# W964.net
KiCad netlist of a schematic drawn in EAGLE
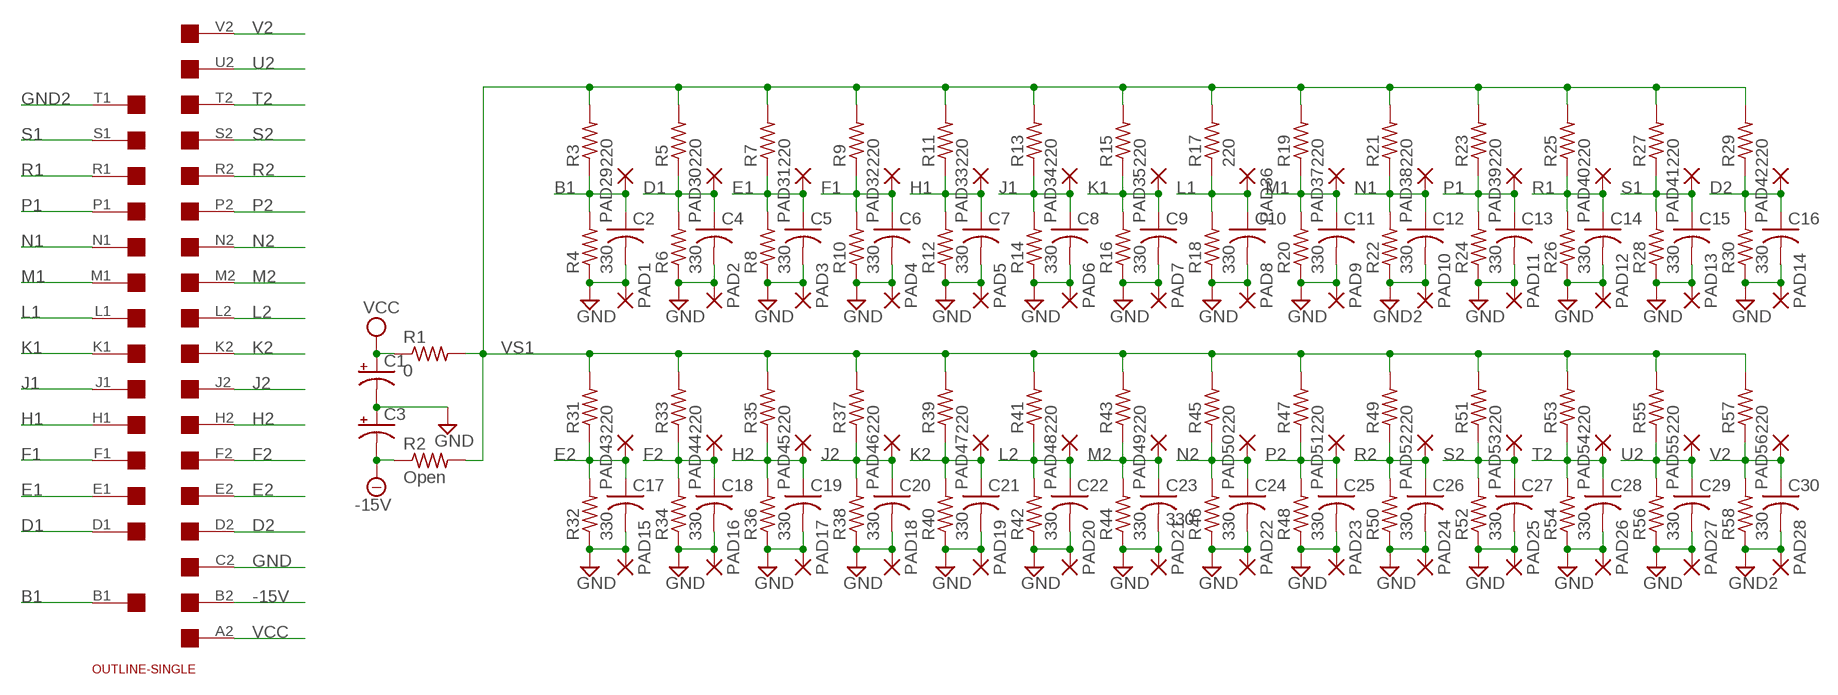
[diagram p0: schematic, sheet 1]

(export (version "E")
  (design (tool "Eeschema 10.0.6"))
  (components
    (comp (ref "C1")
      (value "CPOL-USE22-6AXIAL")
      (footprint "eagle-import:E22-6")
      (libsource (lib "eagle-import") (part "CPOL-USE22-6AXIAL"))
    )
    (comp (ref "C2")
      (value "C-US050-025X075")
      (footprint "eagle-import:C050-025X075")
      (libsource (lib "eagle-import") (part "C-US050-025X075"))
    )
    (comp (ref "C3")
      (value "CPOL-USE22-6AXIAL")
      (footprint "eagle-import:E22-6")
      (libsource (lib "eagle-import") (part "CPOL-USE22-6AXIAL"))
    )
    (comp (ref "C4")
      (value "C-US050-025X075")
      (footprint "eagle-import:C050-025X075")
      (libsource (lib "eagle-import") (part "C-US050-025X075"))
    )
    (comp (ref "C5")
      (value "C-US050-025X075")
      (footprint "eagle-import:C050-025X075")
      (libsource (lib "eagle-import") (part "C-US050-025X075"))
    )
    (comp (ref "C6")
      (value "C-US050-025X075")
      (footprint "eagle-import:C050-025X075")
      (libsource (lib "eagle-import") (part "C-US050-025X075"))
    )
    (comp (ref "C7")
      (value "C-US050-025X075")
      (footprint "eagle-import:C050-025X075")
      (libsource (lib "eagle-import") (part "C-US050-025X075"))
    )
    (comp (ref "C8")
      (value "C-US050-025X075")
      (footprint "eagle-import:C050-025X075")
      (libsource (lib "eagle-import") (part "C-US050-025X075"))
    )
    (comp (ref "C9")
      (value "C-US050-025X075")
      (footprint "eagle-import:C050-025X075")
      (libsource (lib "eagle-import") (part "C-US050-025X075"))
    )
    (comp (ref "C10")
      (value "C-US050-025X075")
      (footprint "eagle-import:C050-025X075")
      (libsource (lib "eagle-import") (part "C-US050-025X075"))
    )
    (comp (ref "C11")
      (value "C-US050-025X075")
      (footprint "eagle-import:C050-025X075")
      (libsource (lib "eagle-import") (part "C-US050-025X075"))
    )
    (comp (ref "C12")
      (value "C-US050-025X075")
      (footprint "eagle-import:C050-025X075")
      (libsource (lib "eagle-import") (part "C-US050-025X075"))
    )
    (comp (ref "C13")
      (value "C-US050-025X075")
      (footprint "eagle-import:C050-025X075")
      (libsource (lib "eagle-import") (part "C-US050-025X075"))
    )
    (comp (ref "C14")
      (value "C-US050-025X075")
      (footprint "eagle-import:C050-025X075")
      (libsource (lib "eagle-import") (part "C-US050-025X075"))
    )
    (comp (ref "C15")
      (value "C-US050-025X075")
      (footprint "eagle-import:C050-025X075")
      (libsource (lib "eagle-import") (part "C-US050-025X075"))
    )
    (comp (ref "C16")
      (value "C-US050-025X075")
      (footprint "eagle-import:C050-025X075")
      (libsource (lib "eagle-import") (part "C-US050-025X075"))
    )
    (comp (ref "C17")
      (value "C-US050-025X075")
      (footprint "eagle-import:C050-025X075")
      (libsource (lib "eagle-import") (part "C-US050-025X075"))
    )
    (comp (ref "C18")
      (value "C-US050-025X075")
      (footprint "eagle-import:C050-025X075")
      (libsource (lib "eagle-import") (part "C-US050-025X075"))
    )
    (comp (ref "C19")
      (value "C-US050-025X075")
      (footprint "eagle-import:C050-025X075")
      (libsource (lib "eagle-import") (part "C-US050-025X075"))
    )
    (comp (ref "C20")
      (value "C-US050-025X075")
      (footprint "eagle-import:C050-025X075")
      (libsource (lib "eagle-import") (part "C-US050-025X075"))
    )
    (comp (ref "C21")
      (value "C-US050-025X075")
      (footprint "eagle-import:C050-025X075")
      (libsource (lib "eagle-import") (part "C-US050-025X075"))
    )
    (comp (ref "C22")
      (value "C-US050-025X075")
      (footprint "eagle-import:C050-025X075")
      (libsource (lib "eagle-import") (part "C-US050-025X075"))
    )
    (comp (ref "C23")
      (value "330")
      (footprint "eagle-import:C050-025X075")
      (libsource (lib "eagle-import") (part "C-US050-025X075"))
    )
    (comp (ref "C24")
      (value "C-US050-025X075")
      (footprint "eagle-import:C050-025X075")
      (libsource (lib "eagle-import") (part "C-US050-025X075"))
    )
    (comp (ref "C25")
      (value "C-US050-025X075")
      (footprint "eagle-import:C050-025X075")
      (libsource (lib "eagle-import") (part "C-US050-025X075"))
    )
    (comp (ref "C26")
      (value "C-US050-025X075")
      (footprint "eagle-import:C050-025X075")
      (libsource (lib "eagle-import") (part "C-US050-025X075"))
    )
    (comp (ref "C27")
      (value "C-US050-025X075")
      (footprint "eagle-import:C050-025X075")
      (libsource (lib "eagle-import") (part "C-US050-025X075"))
    )
    (comp (ref "C28")
      (value "C-US050-025X075")
      (footprint "eagle-import:C050-025X075")
      (libsource (lib "eagle-import") (part "C-US050-025X075"))
    )
    (comp (ref "C29")
      (value "C-US050-025X075")
      (footprint "eagle-import:C050-025X075")
      (libsource (lib "eagle-import") (part "C-US050-025X075"))
    )
    (comp (ref "C30")
      (value "C-US050-025X075")
      (footprint "eagle-import:C050-025X075")
      (libsource (lib "eagle-import") (part "C-US050-025X075"))
    )
    (comp (ref "PAD1")
      (value "1,6/0,9")
      (footprint "eagle-import:1,6_0,9")
      (libsource (lib "eagle-import") (part "1,6/0,9"))
    )
    (comp (ref "PAD2")
      (value "1,6/0,9")
      (footprint "eagle-import:1,6_0,9")
      (libsource (lib "eagle-import") (part "1,6/0,9"))
    )
    (comp (ref "PAD3")
      (value "1,6/0,9")
      (footprint "eagle-import:1,6_0,9")
      (libsource (lib "eagle-import") (part "1,6/0,9"))
    )
    (comp (ref "PAD4")
      (value "1,6/0,9")
      (footprint "eagle-import:1,6_0,9")
      (libsource (lib "eagle-import") (part "1,6/0,9"))
    )
    (comp (ref "PAD5")
      (value "1,6/0,9")
      (footprint "eagle-import:1,6_0,9")
      (libsource (lib "eagle-import") (part "1,6/0,9"))
    )
    (comp (ref "PAD6")
      (value "1,6/0,9")
      (footprint "eagle-import:1,6_0,9")
      (libsource (lib "eagle-import") (part "1,6/0,9"))
    )
    (comp (ref "PAD7")
      (value "1,6/0,9")
      (footprint "eagle-import:1,6_0,9")
      (libsource (lib "eagle-import") (part "1,6/0,9"))
    )
    (comp (ref "PAD8")
      (value "1,6/0,9")
      (footprint "eagle-import:1,6_0,9")
      (libsource (lib "eagle-import") (part "1,6/0,9"))
    )
    (comp (ref "PAD9")
      (value "1,6/0,9")
      (footprint "eagle-import:1,6_0,9")
      (libsource (lib "eagle-import") (part "1,6/0,9"))
    )
    (comp (ref "PAD10")
      (value "1,6/0,9")
      (footprint "eagle-import:1,6_0,9")
      (libsource (lib "eagle-import") (part "1,6/0,9"))
    )
    (comp (ref "PAD11")
      (value "1,6/0,9")
      (footprint "eagle-import:1,6_0,9")
      (libsource (lib "eagle-import") (part "1,6/0,9"))
    )
    (comp (ref "PAD12")
      (value "1,6/0,9")
      (footprint "eagle-import:1,6_0,9")
      (libsource (lib "eagle-import") (part "1,6/0,9"))
    )
    (comp (ref "PAD13")
      (value "1,6/0,9")
      (footprint "eagle-import:1,6_0,9")
      (libsource (lib "eagle-import") (part "1,6/0,9"))
    )
    (comp (ref "PAD14")
      (value "1,6/0,9")
      (footprint "eagle-import:1,6_0,9")
      (libsource (lib "eagle-import") (part "1,6/0,9"))
    )
    (comp (ref "PAD15")
      (value "1,6/0,9")
      (footprint "eagle-import:1,6_0,9")
      (libsource (lib "eagle-import") (part "1,6/0,9"))
    )
    (comp (ref "PAD16")
      (value "1,6/0,9")
      (footprint "eagle-import:1,6_0,9")
      (libsource (lib "eagle-import") (part "1,6/0,9"))
    )
    (comp (ref "PAD17")
      (value "1,6/0,9")
      (footprint "eagle-import:1,6_0,9")
      (libsource (lib "eagle-import") (part "1,6/0,9"))
    )
    (comp (ref "PAD18")
      (value "1,6/0,9")
      (footprint "eagle-import:1,6_0,9")
      (libsource (lib "eagle-import") (part "1,6/0,9"))
    )
    (comp (ref "PAD19")
      (value "1,6/0,9")
      (footprint "eagle-import:1,6_0,9")
      (libsource (lib "eagle-import") (part "1,6/0,9"))
    )
    (comp (ref "PAD20")
      (value "1,6/0,9")
      (footprint "eagle-import:1,6_0,9")
      (libsource (lib "eagle-import") (part "1,6/0,9"))
    )
    (comp (ref "PAD21")
      (value "1,6/0,9")
      (footprint "eagle-import:1,6_0,9")
      (libsource (lib "eagle-import") (part "1,6/0,9"))
    )
    (comp (ref "PAD22")
      (value "1,6/0,9")
      (footprint "eagle-import:1,6_0,9")
      (libsource (lib "eagle-import") (part "1,6/0,9"))
    )
    (comp (ref "PAD23")
      (value "1,6/0,9")
      (footprint "eagle-import:1,6_0,9")
      (libsource (lib "eagle-import") (part "1,6/0,9"))
    )
    (comp (ref "PAD24")
      (value "1,6/0,9")
      (footprint "eagle-import:1,6_0,9")
      (libsource (lib "eagle-import") (part "1,6/0,9"))
    )
    (comp (ref "PAD25")
      (value "1,6/0,9")
      (footprint "eagle-import:1,6_0,9")
      (libsource (lib "eagle-import") (part "1,6/0,9"))
    )
    (comp (ref "PAD26")
      (value "1,6/0,9")
      (footprint "eagle-import:1,6_0,9")
      (libsource (lib "eagle-import") (part "1,6/0,9"))
    )
    (comp (ref "PAD27")
      (value "1,6/0,9")
      (footprint "eagle-import:1,6_0,9")
      (libsource (lib "eagle-import") (part "1,6/0,9"))
    )
    (comp (ref "PAD28")
      (value "1,6/0,9")
      (footprint "eagle-import:1,6_0,9")
      (libsource (lib "eagle-import") (part "1,6/0,9"))
    )
    (comp (ref "PAD29")
      (value "1,6/0,9")
      (footprint "eagle-import:1,6_0,9")
      (libsource (lib "eagle-import") (part "1,6/0,9"))
    )
    (comp (ref "PAD30")
      (value "1,6/0,9")
      (footprint "eagle-import:1,6_0,9")
      (libsource (lib "eagle-import") (part "1,6/0,9"))
    )
    (comp (ref "PAD31")
      (value "1,6/0,9")
      (footprint "eagle-import:1,6_0,9")
      (libsource (lib "eagle-import") (part "1,6/0,9"))
    )
    (comp (ref "PAD32")
      (value "1,6/0,9")
      (footprint "eagle-import:1,6_0,9")
      (libsource (lib "eagle-import") (part "1,6/0,9"))
    )
    (comp (ref "PAD33")
      (value "1,6/0,9")
      (footprint "eagle-import:1,6_0,9")
      (libsource (lib "eagle-import") (part "1,6/0,9"))
    )
    (comp (ref "PAD34")
      (value "1,6/0,9")
      (footprint "eagle-import:1,6_0,9")
      (libsource (lib "eagle-import") (part "1,6/0,9"))
    )
    (comp (ref "PAD35")
      (value "1,6/0,9")
      (footprint "eagle-import:1,6_0,9")
      (libsource (lib "eagle-import") (part "1,6/0,9"))
    )
    (comp (ref "PAD36")
      (value "1,6/0,9")
      (footprint "eagle-import:1,6_0,9")
      (libsource (lib "eagle-import") (part "1,6/0,9"))
    )
    (comp (ref "PAD37")
      (value "1,6/0,9")
      (footprint "eagle-import:1,6_0,9")
      (libsource (lib "eagle-import") (part "1,6/0,9"))
    )
    (comp (ref "PAD38")
      (value "1,6/0,9")
      (footprint "eagle-import:1,6_0,9")
      (libsource (lib "eagle-import") (part "1,6/0,9"))
    )
    (comp (ref "PAD39")
      (value "1,6/0,9")
      (footprint "eagle-import:1,6_0,9")
      (libsource (lib "eagle-import") (part "1,6/0,9"))
    )
    (comp (ref "PAD40")
      (value "1,6/0,9")
      (footprint "eagle-import:1,6_0,9")
      (libsource (lib "eagle-import") (part "1,6/0,9"))
    )
    (comp (ref "PAD41")
      (value "1,6/0,9")
      (footprint "eagle-import:1,6_0,9")
      (libsource (lib "eagle-import") (part "1,6/0,9"))
    )
    (comp (ref "PAD42")
      (value "1,6/0,9")
      (footprint "eagle-import:1,6_0,9")
      (libsource (lib "eagle-import") (part "1,6/0,9"))
    )
    (comp (ref "PAD43")
      (value "1,6/0,9")
      (footprint "eagle-import:1,6_0,9")
      (libsource (lib "eagle-import") (part "1,6/0,9"))
    )
    (comp (ref "PAD44")
      (value "1,6/0,9")
      (footprint "eagle-import:1,6_0,9")
      (libsource (lib "eagle-import") (part "1,6/0,9"))
    )
    (comp (ref "PAD45")
      (value "1,6/0,9")
      (footprint "eagle-import:1,6_0,9")
      (libsource (lib "eagle-import") (part "1,6/0,9"))
    )
    (comp (ref "PAD46")
      (value "1,6/0,9")
      (footprint "eagle-import:1,6_0,9")
      (libsource (lib "eagle-import") (part "1,6/0,9"))
    )
    (comp (ref "PAD47")
      (value "1,6/0,9")
      (footprint "eagle-import:1,6_0,9")
      (libsource (lib "eagle-import") (part "1,6/0,9"))
    )
    (comp (ref "PAD48")
      (value "1,6/0,9")
      (footprint "eagle-import:1,6_0,9")
      (libsource (lib "eagle-import") (part "1,6/0,9"))
    )
    (comp (ref "PAD49")
      (value "1,6/0,9")
      (footprint "eagle-import:1,6_0,9")
      (libsource (lib "eagle-import") (part "1,6/0,9"))
    )
    (comp (ref "PAD50")
      (value "1,6/0,9")
      (footprint "eagle-import:1,6_0,9")
      (libsource (lib "eagle-import") (part "1,6/0,9"))
    )
    (comp (ref "PAD51")
      (value "1,6/0,9")
      (footprint "eagle-import:1,6_0,9")
      (libsource (lib "eagle-import") (part "1,6/0,9"))
    )
    (comp (ref "PAD52")
      (value "1,6/0,9")
      (footprint "eagle-import:1,6_0,9")
      (libsource (lib "eagle-import") (part "1,6/0,9"))
    )
    (comp (ref "PAD53")
      (value "1,6/0,9")
      (footprint "eagle-import:1,6_0,9")
      (libsource (lib "eagle-import") (part "1,6/0,9"))
    )
    (comp (ref "PAD54")
      (value "1,6/0,9")
      (footprint "eagle-import:1,6_0,9")
      (libsource (lib "eagle-import") (part "1,6/0,9"))
    )
    (comp (ref "PAD55")
      (value "1,6/0,9")
      (footprint "eagle-import:1,6_0,9")
      (libsource (lib "eagle-import") (part "1,6/0,9"))
    )
    (comp (ref "PAD56")
      (value "1,6/0,9")
      (footprint "eagle-import:1,6_0,9")
      (libsource (lib "eagle-import") (part "1,6/0,9"))
    )
    (comp (ref "R1")
      (value "0")
      (footprint "eagle-import:0207_10")
      (libsource (lib "eagle-import") (part "R-US_0207/10"))
    )
    (comp (ref "R2")
      (value "Open")
      (footprint "eagle-import:0207_10")
      (libsource (lib "eagle-import") (part "R-US_0207/10"))
    )
    (comp (ref "R3")
      (value "220")
      (footprint "eagle-import:0207_10")
      (libsource (lib "eagle-import") (part "R-US_0207/10"))
    )
    (comp (ref "R4")
      (value "330")
      (footprint "eagle-import:0207_10")
      (libsource (lib "eagle-import") (part "R-US_0207/10"))
    )
    (comp (ref "R5")
      (value "220")
      (footprint "eagle-import:0207_10")
      (libsource (lib "eagle-import") (part "R-US_0207/10"))
    )
    (comp (ref "R6")
      (value "330")
      (footprint "eagle-import:0207_10")
      (libsource (lib "eagle-import") (part "R-US_0207/10"))
    )
    (comp (ref "R7")
      (value "220")
      (footprint "eagle-import:0207_10")
      (libsource (lib "eagle-import") (part "R-US_0207/10"))
    )
    (comp (ref "R8")
      (value "330")
      (footprint "eagle-import:0207_10")
      (libsource (lib "eagle-import") (part "R-US_0207/10"))
    )
    (comp (ref "R9")
      (value "220")
      (footprint "eagle-import:0207_10")
      (libsource (lib "eagle-import") (part "R-US_0207/10"))
    )
    (comp (ref "R10")
      (value "330")
      (footprint "eagle-import:0207_10")
      (libsource (lib "eagle-import") (part "R-US_0207/10"))
    )
    (comp (ref "R11")
      (value "220")
      (footprint "eagle-import:0207_10")
      (libsource (lib "eagle-import") (part "R-US_0207/10"))
    )
    (comp (ref "R12")
      (value "330")
      (footprint "eagle-import:0207_10")
      (libsource (lib "eagle-import") (part "R-US_0207/10"))
    )
    (comp (ref "R13")
      (value "220")
      (footprint "eagle-import:0207_10")
      (libsource (lib "eagle-import") (part "R-US_0207/10"))
    )
    (comp (ref "R14")
      (value "330")
      (footprint "eagle-import:0207_10")
      (libsource (lib "eagle-import") (part "R-US_0207/10"))
    )
    (comp (ref "R15")
      (value "220")
      (footprint "eagle-import:0207_10")
      (libsource (lib "eagle-import") (part "R-US_0207/10"))
    )
    (comp (ref "R16")
      (value "330")
      (footprint "eagle-import:0207_10")
      (libsource (lib "eagle-import") (part "R-US_0207/10"))
    )
    (comp (ref "R17")
      (value "220")
      (footprint "eagle-import:0207_10")
      (libsource (lib "eagle-import") (part "R-US_0207/10"))
    )
    (comp (ref "R18")
      (value "330")
      (footprint "eagle-import:0207_10")
      (libsource (lib "eagle-import") (part "R-US_0207/10"))
    )
    (comp (ref "R19")
      (value "220")
      (footprint "eagle-import:0207_10")
      (libsource (lib "eagle-import") (part "R-US_0207/10"))
    )
    (comp (ref "R20")
      (value "330")
      (footprint "eagle-import:0207_10")
      (libsource (lib "eagle-import") (part "R-US_0207/10"))
    )
    (comp (ref "R21")
      (value "220")
      (footprint "eagle-import:0207_10")
      (libsource (lib "eagle-import") (part "R-US_0207/10"))
    )
    (comp (ref "R22")
      (value "330")
      (footprint "eagle-import:0207_10")
      (libsource (lib "eagle-import") (part "R-US_0207/10"))
    )
    (comp (ref "R23")
      (value "220")
      (footprint "eagle-import:0207_10")
      (libsource (lib "eagle-import") (part "R-US_0207/10"))
    )
    (comp (ref "R24")
      (value "330")
      (footprint "eagle-import:0207_10")
      (libsource (lib "eagle-import") (part "R-US_0207/10"))
    )
    (comp (ref "R25")
      (value "220")
      (footprint "eagle-import:0207_10")
      (libsource (lib "eagle-import") (part "R-US_0207/10"))
    )
    (comp (ref "R26")
      (value "330")
      (footprint "eagle-import:0207_10")
      (libsource (lib "eagle-import") (part "R-US_0207/10"))
    )
    (comp (ref "R27")
      (value "220")
      (footprint "eagle-import:0207_10")
      (libsource (lib "eagle-import") (part "R-US_0207/10"))
    )
    (comp (ref "R28")
      (value "330")
      (footprint "eagle-import:0207_10")
      (libsource (lib "eagle-import") (part "R-US_0207/10"))
    )
    (comp (ref "R29")
      (value "220")
      (footprint "eagle-import:0207_10")
      (libsource (lib "eagle-import") (part "R-US_0207/10"))
    )
    (comp (ref "R30")
      (value "330")
      (footprint "eagle-import:0207_10")
      (libsource (lib "eagle-import") (part "R-US_0207/10"))
    )
    (comp (ref "R31")
      (value "220")
      (footprint "eagle-import:0207_10")
      (libsource (lib "eagle-import") (part "R-US_0207/10"))
    )
    (comp (ref "R32")
      (value "330")
      (footprint "eagle-import:0207_10")
      (libsource (lib "eagle-import") (part "R-US_0207/10"))
    )
    (comp (ref "R33")
      (value "220")
      (footprint "eagle-import:0207_10")
      (libsource (lib "eagle-import") (part "R-US_0207/10"))
    )
    (comp (ref "R34")
      (value "330")
      (footprint "eagle-import:0207_10")
      (libsource (lib "eagle-import") (part "R-US_0207/10"))
    )
    (comp (ref "R35")
      (value "220")
      (footprint "eagle-import:0207_10")
      (libsource (lib "eagle-import") (part "R-US_0207/10"))
    )
    (comp (ref "R36")
      (value "330")
      (footprint "eagle-import:0207_10")
      (libsource (lib "eagle-import") (part "R-US_0207/10"))
    )
    (comp (ref "R37")
      (value "220")
      (footprint "eagle-import:0207_10")
      (libsource (lib "eagle-import") (part "R-US_0207/10"))
    )
    (comp (ref "R38")
      (value "330")
      (footprint "eagle-import:0207_10")
      (libsource (lib "eagle-import") (part "R-US_0207/10"))
    )
    (comp (ref "R39")
      (value "220")
      (footprint "eagle-import:0207_10")
      (libsource (lib "eagle-import") (part "R-US_0207/10"))
    )
    (comp (ref "R40")
      (value "330")
      (footprint "eagle-import:0207_10")
      (libsource (lib "eagle-import") (part "R-US_0207/10"))
    )
    (comp (ref "R41")
      (value "220")
      (footprint "eagle-import:0207_10")
      (libsource (lib "eagle-import") (part "R-US_0207/10"))
    )
    (comp (ref "R42")
      (value "330")
      (footprint "eagle-import:0207_10")
      (libsource (lib "eagle-import") (part "R-US_0207/10"))
    )
    (comp (ref "R43")
      (value "220")
      (footprint "eagle-import:0207_10")
      (libsource (lib "eagle-import") (part "R-US_0207/10"))
    )
    (comp (ref "R44")
      (value "330")
      (footprint "eagle-import:0207_10")
      (libsource (lib "eagle-import") (part "R-US_0207/10"))
    )
    (comp (ref "R45")
      (value "220")
      (footprint "eagle-import:0207_10")
      (libsource (lib "eagle-import") (part "R-US_0207/10"))
    )
    (comp (ref "R46")
      (value "330")
      (footprint "eagle-import:0207_10")
      (libsource (lib "eagle-import") (part "R-US_0207/10"))
    )
    (comp (ref "R47")
      (value "220")
      (footprint "eagle-import:0207_10")
      (libsource (lib "eagle-import") (part "R-US_0207/10"))
    )
    (comp (ref "R48")
      (value "330")
      (footprint "eagle-import:0207_10")
      (libsource (lib "eagle-import") (part "R-US_0207/10"))
    )
    (comp (ref "R49")
      (value "220")
      (footprint "eagle-import:0207_10")
      (libsource (lib "eagle-import") (part "R-US_0207/10"))
    )
    (comp (ref "R50")
      (value "330")
      (footprint "eagle-import:0207_10")
      (libsource (lib "eagle-import") (part "R-US_0207/10"))
    )
    (comp (ref "R51")
      (value "220")
      (footprint "eagle-import:0207_10")
      (libsource (lib "eagle-import") (part "R-US_0207/10"))
    )
    (comp (ref "R52")
      (value "330")
      (footprint "eagle-import:0207_10")
      (libsource (lib "eagle-import") (part "R-US_0207/10"))
    )
    (comp (ref "R53")
      (value "220")
      (footprint "eagle-import:0207_10")
      (libsource (lib "eagle-import") (part "R-US_0207/10"))
    )
    (comp (ref "R54")
      (value "330")
      (footprint "eagle-import:0207_10")
      (libsource (lib "eagle-import") (part "R-US_0207/10"))
    )
    (comp (ref "R55")
      (value "220")
      (footprint "eagle-import:0207_10")
      (libsource (lib "eagle-import") (part "R-US_0207/10"))
    )
    (comp (ref "R56")
      (value "330")
      (footprint "eagle-import:0207_10")
      (libsource (lib "eagle-import") (part "R-US_0207/10"))
    )
    (comp (ref "R57")
      (value "220")
      (footprint "eagle-import:0207_10")
      (libsource (lib "eagle-import") (part "R-US_0207/10"))
    )
    (comp (ref "R58")
      (value "330")
      (footprint "eagle-import:0207_10")
      (libsource (lib "eagle-import") (part "R-US_0207/10"))
    )
    (comp (ref "U$1")
      (value "EDGE-2CONNECTOR")
      (footprint "eagle-import:EDGE-CON2")
      (libsource (lib "eagle-import") (part "EDGE-2CONNECTOR"))
    )
    (comp (ref "U$2")
      (value "OUTLINE-SINGLE")
      (footprint "eagle-import:SINGLE")
      (libsource (lib "eagle-import") (part "OUTLINE-SINGLE"))
    )
  )
  (nets
    (net (code "1") (name "-15V") (class "Default")
      (node (ref "C3") (pin "-") (pinfunction "-_-") (pintype "passive"))
      (node (ref "R2") (pin "1") (pinfunction "1_1") (pintype "passive"))
      (node (ref "U$1") (pin "B2") (pinfunction "1_B2") (pintype "bidirectional"))
    )
    (net (code "2") (name "/B1") (class "Default")
      (node (ref "C2") (pin "1") (pinfunction "1_1") (pintype "passive"))
      (node (ref "PAD29") (pin "1") (pinfunction "P_1") (pintype "passive"))
      (node (ref "R3") (pin "1") (pinfunction "1_1") (pintype "passive"))
      (node (ref "R4") (pin "2") (pinfunction "2_2") (pintype "passive"))
      (node (ref "U$1") (pin "B1") (pinfunction "1_B1") (pintype "bidirectional"))
    )
    (net (code "3") (name "/D1") (class "Default")
      (node (ref "C4") (pin "1") (pinfunction "1_1") (pintype "passive"))
      (node (ref "PAD30") (pin "1") (pinfunction "P_1") (pintype "passive"))
      (node (ref "R5") (pin "1") (pinfunction "1_1") (pintype "passive"))
      (node (ref "R6") (pin "2") (pinfunction "2_2") (pintype "passive"))
      (node (ref "U$1") (pin "D1") (pinfunction "1_D1") (pintype "bidirectional"))
    )
    (net (code "4") (name "/D2") (class "Default")
      (node (ref "C16") (pin "1") (pinfunction "1_1") (pintype "passive"))
      (node (ref "PAD42") (pin "1") (pinfunction "P_1") (pintype "passive"))
      (node (ref "R29") (pin "1") (pinfunction "1_1") (pintype "passive"))
      (node (ref "R30") (pin "2") (pinfunction "2_2") (pintype "passive"))
      (node (ref "U$1") (pin "D2") (pinfunction "1_D2") (pintype "bidirectional"))
    )
    (net (code "5") (name "/E1") (class "Default")
      (node (ref "C5") (pin "1") (pinfunction "1_1") (pintype "passive"))
      (node (ref "PAD31") (pin "1") (pinfunction "P_1") (pintype "passive"))
      (node (ref "R7") (pin "1") (pinfunction "1_1") (pintype "passive"))
      (node (ref "R8") (pin "2") (pinfunction "2_2") (pintype "passive"))
      (node (ref "U$1") (pin "E1") (pinfunction "1_E1") (pintype "bidirectional"))
    )
    (net (code "6") (name "/E2") (class "Default")
      (node (ref "C17") (pin "1") (pinfunction "1_1") (pintype "passive"))
      (node (ref "PAD43") (pin "1") (pinfunction "P_1") (pintype "passive"))
      (node (ref "R31") (pin "1") (pinfunction "1_1") (pintype "passive"))
      (node (ref "R32") (pin "2") (pinfunction "2_2") (pintype "passive"))
      (node (ref "U$1") (pin "E2") (pinfunction "1_E2") (pintype "bidirectional"))
    )
    (net (code "7") (name "/F1") (class "Default")
      (node (ref "C6") (pin "1") (pinfunction "1_1") (pintype "passive"))
      (node (ref "PAD32") (pin "1") (pinfunction "P_1") (pintype "passive"))
      (node (ref "R10") (pin "2") (pinfunction "2_2") (pintype "passive"))
      (node (ref "R9") (pin "1") (pinfunction "1_1") (pintype "passive"))
      (node (ref "U$1") (pin "F1") (pinfunction "1_F1") (pintype "bidirectional"))
    )
    (net (code "8") (name "/F2") (class "Default")
      (node (ref "C18") (pin "1") (pinfunction "1_1") (pintype "passive"))
      (node (ref "PAD44") (pin "1") (pinfunction "P_1") (pintype "passive"))
      (node (ref "R33") (pin "1") (pinfunction "1_1") (pintype "passive"))
      (node (ref "R34") (pin "2") (pinfunction "2_2") (pintype "passive"))
      (node (ref "U$1") (pin "F2") (pinfunction "1_F2") (pintype "bidirectional"))
    )
    (net (code "9") (name "/H1") (class "Default")
      (node (ref "C7") (pin "1") (pinfunction "1_1") (pintype "passive"))
      (node (ref "PAD33") (pin "1") (pinfunction "P_1") (pintype "passive"))
      (node (ref "R11") (pin "1") (pinfunction "1_1") (pintype "passive"))
      (node (ref "R12") (pin "2") (pinfunction "2_2") (pintype "passive"))
      (node (ref "U$1") (pin "H1") (pinfunction "1_H1") (pintype "bidirectional"))
    )
    (net (code "10") (name "/H2") (class "Default")
      (node (ref "C19") (pin "1") (pinfunction "1_1") (pintype "passive"))
      (node (ref "PAD45") (pin "1") (pinfunction "P_1") (pintype "passive"))
      (node (ref "R35") (pin "1") (pinfunction "1_1") (pintype "passive"))
      (node (ref "R36") (pin "2") (pinfunction "2_2") (pintype "passive"))
      (node (ref "U$1") (pin "H2") (pinfunction "1_H2") (pintype "bidirectional"))
    )
    (net (code "11") (name "/J1") (class "Default")
      (node (ref "C8") (pin "1") (pinfunction "1_1") (pintype "passive"))
      (node (ref "PAD34") (pin "1") (pinfunction "P_1") (pintype "passive"))
      (node (ref "R13") (pin "1") (pinfunction "1_1") (pintype "passive"))
      (node (ref "R14") (pin "2") (pinfunction "2_2") (pintype "passive"))
      (node (ref "U$1") (pin "J1") (pinfunction "1_J1") (pintype "bidirectional"))
    )
    (net (code "12") (name "/J2") (class "Default")
      (node (ref "C20") (pin "1") (pinfunction "1_1") (pintype "passive"))
      (node (ref "PAD46") (pin "1") (pinfunction "P_1") (pintype "passive"))
      (node (ref "R37") (pin "1") (pinfunction "1_1") (pintype "passive"))
      (node (ref "R38") (pin "2") (pinfunction "2_2") (pintype "passive"))
      (node (ref "U$1") (pin "J2") (pinfunction "1_J2") (pintype "bidirectional"))
    )
    (net (code "13") (name "/K1") (class "Default")
      (node (ref "C9") (pin "1") (pinfunction "1_1") (pintype "passive"))
      (node (ref "PAD35") (pin "1") (pinfunction "P_1") (pintype "passive"))
      (node (ref "R15") (pin "1") (pinfunction "1_1") (pintype "passive"))
      (node (ref "R16") (pin "2") (pinfunction "2_2") (pintype "passive"))
      (node (ref "U$1") (pin "K1") (pinfunction "1_K1") (pintype "bidirectional"))
    )
    (net (code "14") (name "/K2") (class "Default")
      (node (ref "C21") (pin "1") (pinfunction "1_1") (pintype "passive"))
      (node (ref "PAD47") (pin "1") (pinfunction "P_1") (pintype "passive"))
      (node (ref "R39") (pin "1") (pinfunction "1_1") (pintype "passive"))
      (node (ref "R40") (pin "2") (pinfunction "2_2") (pintype "passive"))
      (node (ref "U$1") (pin "K2") (pinfunction "1_K2") (pintype "bidirectional"))
    )
    (net (code "15") (name "/L1") (class "Default")
      (node (ref "C10") (pin "1") (pinfunction "1_1") (pintype "passive"))
      (node (ref "PAD36") (pin "1") (pinfunction "P_1") (pintype "passive"))
      (node (ref "R17") (pin "1") (pinfunction "1_1") (pintype "passive"))
      (node (ref "R18") (pin "2") (pinfunction "2_2") (pintype "passive"))
      (node (ref "U$1") (pin "L1") (pinfunction "1_L1") (pintype "bidirectional"))
    )
    (net (code "16") (name "/L2") (class "Default")
      (node (ref "C22") (pin "1") (pinfunction "1_1") (pintype "passive"))
      (node (ref "PAD48") (pin "1") (pinfunction "P_1") (pintype "passive"))
      (node (ref "R41") (pin "1") (pinfunction "1_1") (pintype "passive"))
      (node (ref "R42") (pin "2") (pinfunction "2_2") (pintype "passive"))
      (node (ref "U$1") (pin "L2") (pinfunction "1_L2") (pintype "bidirectional"))
    )
    (net (code "17") (name "/M1") (class "Default")
      (node (ref "C11") (pin "1") (pinfunction "1_1") (pintype "passive"))
      (node (ref "PAD37") (pin "1") (pinfunction "P_1") (pintype "passive"))
      (node (ref "R19") (pin "1") (pinfunction "1_1") (pintype "passive"))
      (node (ref "R20") (pin "2") (pinfunction "2_2") (pintype "passive"))
      (node (ref "U$1") (pin "M1") (pinfunction "1_M1") (pintype "bidirectional"))
    )
    (net (code "18") (name "/M2") (class "Default")
      (node (ref "C23") (pin "1") (pinfunction "1_1") (pintype "passive"))
      (node (ref "PAD49") (pin "1") (pinfunction "P_1") (pintype "passive"))
      (node (ref "R43") (pin "1") (pinfunction "1_1") (pintype "passive"))
      (node (ref "R44") (pin "2") (pinfunction "2_2") (pintype "passive"))
      (node (ref "U$1") (pin "M2") (pinfunction "1_M2") (pintype "bidirectional"))
    )
    (net (code "19") (name "/N1") (class "Default")
      (node (ref "C12") (pin "1") (pinfunction "1_1") (pintype "passive"))
      (node (ref "PAD38") (pin "1") (pinfunction "P_1") (pintype "passive"))
      (node (ref "R21") (pin "1") (pinfunction "1_1") (pintype "passive"))
      (node (ref "R22") (pin "2") (pinfunction "2_2") (pintype "passive"))
      (node (ref "U$1") (pin "N1") (pinfunction "1_N1") (pintype "bidirectional"))
    )
    (net (code "20") (name "/N2") (class "Default")
      (node (ref "C24") (pin "1") (pinfunction "1_1") (pintype "passive"))
      (node (ref "PAD50") (pin "1") (pinfunction "P_1") (pintype "passive"))
      (node (ref "R45") (pin "1") (pinfunction "1_1") (pintype "passive"))
      (node (ref "R46") (pin "2") (pinfunction "2_2") (pintype "passive"))
      (node (ref "U$1") (pin "N2") (pinfunction "1_N2") (pintype "bidirectional"))
    )
    (net (code "21") (name "/P1") (class "Default")
      (node (ref "C13") (pin "1") (pinfunction "1_1") (pintype "passive"))
      (node (ref "PAD39") (pin "1") (pinfunction "P_1") (pintype "passive"))
      (node (ref "R23") (pin "1") (pinfunction "1_1") (pintype "passive"))
      (node (ref "R24") (pin "2") (pinfunction "2_2") (pintype "passive"))
      (node (ref "U$1") (pin "P1") (pinfunction "1_P1") (pintype "bidirectional"))
    )
    (net (code "22") (name "/P2") (class "Default")
      (node (ref "C25") (pin "1") (pinfunction "1_1") (pintype "passive"))
      (node (ref "PAD51") (pin "1") (pinfunction "P_1") (pintype "passive"))
      (node (ref "R47") (pin "1") (pinfunction "1_1") (pintype "passive"))
      (node (ref "R48") (pin "2") (pinfunction "2_2") (pintype "passive"))
      (node (ref "U$1") (pin "P2") (pinfunction "1_P2") (pintype "bidirectional"))
    )
    (net (code "23") (name "/R1") (class "Default")
      (node (ref "C14") (pin "1") (pinfunction "1_1") (pintype "passive"))
      (node (ref "PAD40") (pin "1") (pinfunction "P_1") (pintype "passive"))
      (node (ref "R25") (pin "1") (pinfunction "1_1") (pintype "passive"))
      (node (ref "R26") (pin "2") (pinfunction "2_2") (pintype "passive"))
      (node (ref "U$1") (pin "R1") (pinfunction "1_R1") (pintype "bidirectional"))
    )
    (net (code "24") (name "/R2") (class "Default")
      (node (ref "C26") (pin "1") (pinfunction "1_1") (pintype "passive"))
      (node (ref "PAD52") (pin "1") (pinfunction "P_1") (pintype "passive"))
      (node (ref "R49") (pin "1") (pinfunction "1_1") (pintype "passive"))
      (node (ref "R50") (pin "2") (pinfunction "2_2") (pintype "passive"))
      (node (ref "U$1") (pin "R2") (pinfunction "1_R2") (pintype "bidirectional"))
    )
    (net (code "25") (name "/S1") (class "Default")
      (node (ref "C15") (pin "1") (pinfunction "1_1") (pintype "passive"))
      (node (ref "PAD41") (pin "1") (pinfunction "P_1") (pintype "passive"))
      (node (ref "R27") (pin "1") (pinfunction "1_1") (pintype "passive"))
      (node (ref "R28") (pin "2") (pinfunction "2_2") (pintype "passive"))
      (node (ref "U$1") (pin "S1") (pinfunction "1_S1") (pintype "bidirectional"))
    )
    (net (code "26") (name "/S2") (class "Default")
      (node (ref "C27") (pin "1") (pinfunction "1_1") (pintype "passive"))
      (node (ref "PAD53") (pin "1") (pinfunction "P_1") (pintype "passive"))
      (node (ref "R51") (pin "1") (pinfunction "1_1") (pintype "passive"))
      (node (ref "R52") (pin "2") (pinfunction "2_2") (pintype "passive"))
      (node (ref "U$1") (pin "S2") (pinfunction "1_S2") (pintype "bidirectional"))
    )
    (net (code "27") (name "/T2") (class "Default")
      (node (ref "C28") (pin "1") (pinfunction "1_1") (pintype "passive"))
      (node (ref "PAD54") (pin "1") (pinfunction "P_1") (pintype "passive"))
      (node (ref "R53") (pin "1") (pinfunction "1_1") (pintype "passive"))
      (node (ref "R54") (pin "2") (pinfunction "2_2") (pintype "passive"))
      (node (ref "U$1") (pin "T2") (pinfunction "1_T2") (pintype "bidirectional"))
    )
    (net (code "28") (name "/U2") (class "Default")
      (node (ref "C29") (pin "1") (pinfunction "1_1") (pintype "passive"))
      (node (ref "PAD55") (pin "1") (pinfunction "P_1") (pintype "passive"))
      (node (ref "R55") (pin "1") (pinfunction "1_1") (pintype "passive"))
      (node (ref "R56") (pin "2") (pinfunction "2_2") (pintype "passive"))
      (node (ref "U$1") (pin "U2") (pinfunction "1_U2") (pintype "bidirectional"))
    )
    (net (code "29") (name "/V2") (class "Default")
      (node (ref "C30") (pin "1") (pinfunction "1_1") (pintype "passive"))
      (node (ref "PAD56") (pin "1") (pinfunction "P_1") (pintype "passive"))
      (node (ref "R57") (pin "1") (pinfunction "1_1") (pintype "passive"))
      (node (ref "R58") (pin "2") (pinfunction "2_2") (pintype "passive"))
      (node (ref "U$1") (pin "V2") (pinfunction "1_V2") (pintype "bidirectional"))
    )
    (net (code "30") (name "/VS1") (class "Default")
      (node (ref "R1") (pin "2") (pinfunction "2_2") (pintype "passive"))
      (node (ref "R11") (pin "2") (pinfunction "2_2") (pintype "passive"))
      (node (ref "R13") (pin "2") (pinfunction "2_2") (pintype "passive"))
      (node (ref "R15") (pin "2") (pinfunction "2_2") (pintype "passive"))
      (node (ref "R17") (pin "2") (pinfunction "2_2") (pintype "passive"))
      (node (ref "R19") (pin "2") (pinfunction "2_2") (pintype "passive"))
      (node (ref "R2") (pin "2") (pinfunction "2_2") (pintype "passive"))
      (node (ref "R21") (pin "2") (pinfunction "2_2") (pintype "passive"))
      (node (ref "R23") (pin "2") (pinfunction "2_2") (pintype "passive"))
      (node (ref "R25") (pin "2") (pinfunction "2_2") (pintype "passive"))
      (node (ref "R27") (pin "2") (pinfunction "2_2") (pintype "passive"))
      (node (ref "R29") (pin "2") (pinfunction "2_2") (pintype "passive"))
      (node (ref "R3") (pin "2") (pinfunction "2_2") (pintype "passive"))
      (node (ref "R31") (pin "2") (pinfunction "2_2") (pintype "passive"))
      (node (ref "R33") (pin "2") (pinfunction "2_2") (pintype "passive"))
      (node (ref "R35") (pin "2") (pinfunction "2_2") (pintype "passive"))
      (node (ref "R37") (pin "2") (pinfunction "2_2") (pintype "passive"))
      (node (ref "R39") (pin "2") (pinfunction "2_2") (pintype "passive"))
      (node (ref "R41") (pin "2") (pinfunction "2_2") (pintype "passive"))
      (node (ref "R43") (pin "2") (pinfunction "2_2") (pintype "passive"))
      (node (ref "R45") (pin "2") (pinfunction "2_2") (pintype "passive"))
      (node (ref "R47") (pin "2") (pinfunction "2_2") (pintype "passive"))
      (node (ref "R49") (pin "2") (pinfunction "2_2") (pintype "passive"))
      (node (ref "R5") (pin "2") (pinfunction "2_2") (pintype "passive"))
      (node (ref "R51") (pin "2") (pinfunction "2_2") (pintype "passive"))
      (node (ref "R53") (pin "2") (pinfunction "2_2") (pintype "passive"))
      (node (ref "R55") (pin "2") (pinfunction "2_2") (pintype "passive"))
      (node (ref "R57") (pin "2") (pinfunction "2_2") (pintype "passive"))
      (node (ref "R7") (pin "2") (pinfunction "2_2") (pintype "passive"))
      (node (ref "R9") (pin "2") (pinfunction "2_2") (pintype "passive"))
    )
    (net (code "31") (name "GND") (class "Default")
      (node (ref "C1") (pin "-") (pinfunction "-_-") (pintype "passive"))
      (node (ref "C10") (pin "2") (pinfunction "2_2") (pintype "passive"))
      (node (ref "C11") (pin "2") (pinfunction "2_2") (pintype "passive"))
      (node (ref "C13") (pin "2") (pinfunction "2_2") (pintype "passive"))
      (node (ref "C14") (pin "2") (pinfunction "2_2") (pintype "passive"))
      (node (ref "C15") (pin "2") (pinfunction "2_2") (pintype "passive"))
      (node (ref "C16") (pin "2") (pinfunction "2_2") (pintype "passive"))
      (node (ref "C17") (pin "2") (pinfunction "2_2") (pintype "passive"))
      (node (ref "C18") (pin "2") (pinfunction "2_2") (pintype "passive"))
      (node (ref "C19") (pin "2") (pinfunction "2_2") (pintype "passive"))
      (node (ref "C2") (pin "2") (pinfunction "2_2") (pintype "passive"))
      (node (ref "C20") (pin "2") (pinfunction "2_2") (pintype "passive"))
      (node (ref "C21") (pin "2") (pinfunction "2_2") (pintype "passive"))
      (node (ref "C22") (pin "2") (pinfunction "2_2") (pintype "passive"))
      (node (ref "C23") (pin "2") (pinfunction "2_2") (pintype "passive"))
      (node (ref "C24") (pin "2") (pinfunction "2_2") (pintype "passive"))
      (node (ref "C25") (pin "2") (pinfunction "2_2") (pintype "passive"))
      (node (ref "C26") (pin "2") (pinfunction "2_2") (pintype "passive"))
      (node (ref "C27") (pin "2") (pinfunction "2_2") (pintype "passive"))
      (node (ref "C28") (pin "2") (pinfunction "2_2") (pintype "passive"))
      (node (ref "C29") (pin "2") (pinfunction "2_2") (pintype "passive"))
      (node (ref "C3") (pin "+") (pinfunction "+_+") (pintype "passive"))
      (node (ref "C4") (pin "2") (pinfunction "2_2") (pintype "passive"))
      (node (ref "C5") (pin "2") (pinfunction "2_2") (pintype "passive"))
      (node (ref "C6") (pin "2") (pinfunction "2_2") (pintype "passive"))
      (node (ref "C7") (pin "2") (pinfunction "2_2") (pintype "passive"))
      (node (ref "C8") (pin "2") (pinfunction "2_2") (pintype "passive"))
      (node (ref "C9") (pin "2") (pinfunction "2_2") (pintype "passive"))
      (node (ref "PAD1") (pin "1") (pinfunction "P_1") (pintype "passive"))
      (node (ref "PAD11") (pin "1") (pinfunction "P_1") (pintype "passive"))
      (node (ref "PAD12") (pin "1") (pinfunction "P_1") (pintype "passive"))
      (node (ref "PAD13") (pin "1") (pinfunction "P_1") (pintype "passive"))
      (node (ref "PAD14") (pin "1") (pinfunction "P_1") (pintype "passive"))
      (node (ref "PAD15") (pin "1") (pinfunction "P_1") (pintype "passive"))
      (node (ref "PAD16") (pin "1") (pinfunction "P_1") (pintype "passive"))
      (node (ref "PAD17") (pin "1") (pinfunction "P_1") (pintype "passive"))
      (node (ref "PAD18") (pin "1") (pinfunction "P_1") (pintype "passive"))
      (node (ref "PAD19") (pin "1") (pinfunction "P_1") (pintype "passive"))
      (node (ref "PAD2") (pin "1") (pinfunction "P_1") (pintype "passive"))
      (node (ref "PAD20") (pin "1") (pinfunction "P_1") (pintype "passive"))
      (node (ref "PAD21") (pin "1") (pinfunction "P_1") (pintype "passive"))
      (node (ref "PAD22") (pin "1") (pinfunction "P_1") (pintype "passive"))
      (node (ref "PAD23") (pin "1") (pinfunction "P_1") (pintype "passive"))
      (node (ref "PAD24") (pin "1") (pinfunction "P_1") (pintype "passive"))
      (node (ref "PAD25") (pin "1") (pinfunction "P_1") (pintype "passive"))
      (node (ref "PAD26") (pin "1") (pinfunction "P_1") (pintype "passive"))
      (node (ref "PAD27") (pin "1") (pinfunction "P_1") (pintype "passive"))
      (node (ref "PAD3") (pin "1") (pinfunction "P_1") (pintype "passive"))
      (node (ref "PAD4") (pin "1") (pinfunction "P_1") (pintype "passive"))
      (node (ref "PAD5") (pin "1") (pinfunction "P_1") (pintype "passive"))
      (node (ref "PAD6") (pin "1") (pinfunction "P_1") (pintype "passive"))
      (node (ref "PAD7") (pin "1") (pinfunction "P_1") (pintype "passive"))
      (node (ref "PAD8") (pin "1") (pinfunction "P_1") (pintype "passive"))
      (node (ref "PAD9") (pin "1") (pinfunction "P_1") (pintype "passive"))
      (node (ref "R10") (pin "1") (pinfunction "1_1") (pintype "passive"))
      (node (ref "R12") (pin "1") (pinfunction "1_1") (pintype "passive"))
      (node (ref "R14") (pin "1") (pinfunction "1_1") (pintype "passive"))
      (node (ref "R16") (pin "1") (pinfunction "1_1") (pintype "passive"))
      (node (ref "R18") (pin "1") (pinfunction "1_1") (pintype "passive"))
      (node (ref "R20") (pin "1") (pinfunction "1_1") (pintype "passive"))
      (node (ref "R24") (pin "1") (pinfunction "1_1") (pintype "passive"))
      (node (ref "R26") (pin "1") (pinfunction "1_1") (pintype "passive"))
      (node (ref "R28") (pin "1") (pinfunction "1_1") (pintype "passive"))
      (node (ref "R30") (pin "1") (pinfunction "1_1") (pintype "passive"))
      (node (ref "R32") (pin "1") (pinfunction "1_1") (pintype "passive"))
      (node (ref "R34") (pin "1") (pinfunction "1_1") (pintype "passive"))
      (node (ref "R36") (pin "1") (pinfunction "1_1") (pintype "passive"))
      (node (ref "R38") (pin "1") (pinfunction "1_1") (pintype "passive"))
      (node (ref "R4") (pin "1") (pinfunction "1_1") (pintype "passive"))
      (node (ref "R40") (pin "1") (pinfunction "1_1") (pintype "passive"))
      (node (ref "R42") (pin "1") (pinfunction "1_1") (pintype "passive"))
      (node (ref "R44") (pin "1") (pinfunction "1_1") (pintype "passive"))
      (node (ref "R46") (pin "1") (pinfunction "1_1") (pintype "passive"))
      (node (ref "R48") (pin "1") (pinfunction "1_1") (pintype "passive"))
      (node (ref "R50") (pin "1") (pinfunction "1_1") (pintype "passive"))
      (node (ref "R52") (pin "1") (pinfunction "1_1") (pintype "passive"))
      (node (ref "R54") (pin "1") (pinfunction "1_1") (pintype "passive"))
      (node (ref "R56") (pin "1") (pinfunction "1_1") (pintype "passive"))
      (node (ref "R6") (pin "1") (pinfunction "1_1") (pintype "passive"))
      (node (ref "R8") (pin "1") (pinfunction "1_1") (pintype "passive"))
      (node (ref "U$1") (pin "C2") (pinfunction "1_C2") (pintype "bidirectional"))
    )
    (net (code "32") (name "GND2") (class "Default")
      (node (ref "C12") (pin "2") (pinfunction "2_2") (pintype "passive"))
      (node (ref "C30") (pin "2") (pinfunction "2_2") (pintype "passive"))
      (node (ref "PAD10") (pin "1") (pinfunction "P_1") (pintype "passive"))
      (node (ref "PAD28") (pin "1") (pinfunction "P_1") (pintype "passive"))
      (node (ref "R22") (pin "1") (pinfunction "1_1") (pintype "passive"))
      (node (ref "R58") (pin "1") (pinfunction "1_1") (pintype "passive"))
      (node (ref "U$1") (pin "T1") (pinfunction "1_T1") (pintype "bidirectional"))
    )
    (net (code "33") (name "VCC") (class "Default")
      (node (ref "C1") (pin "+") (pinfunction "+_+") (pintype "passive"))
      (node (ref "R1") (pin "1") (pinfunction "1_1") (pintype "passive"))
      (node (ref "U$1") (pin "A2") (pinfunction "1_A2") (pintype "bidirectional"))
    )
  )
)
